# MCU.net
KiCad netlist of a schematic drawn in Altium Designer
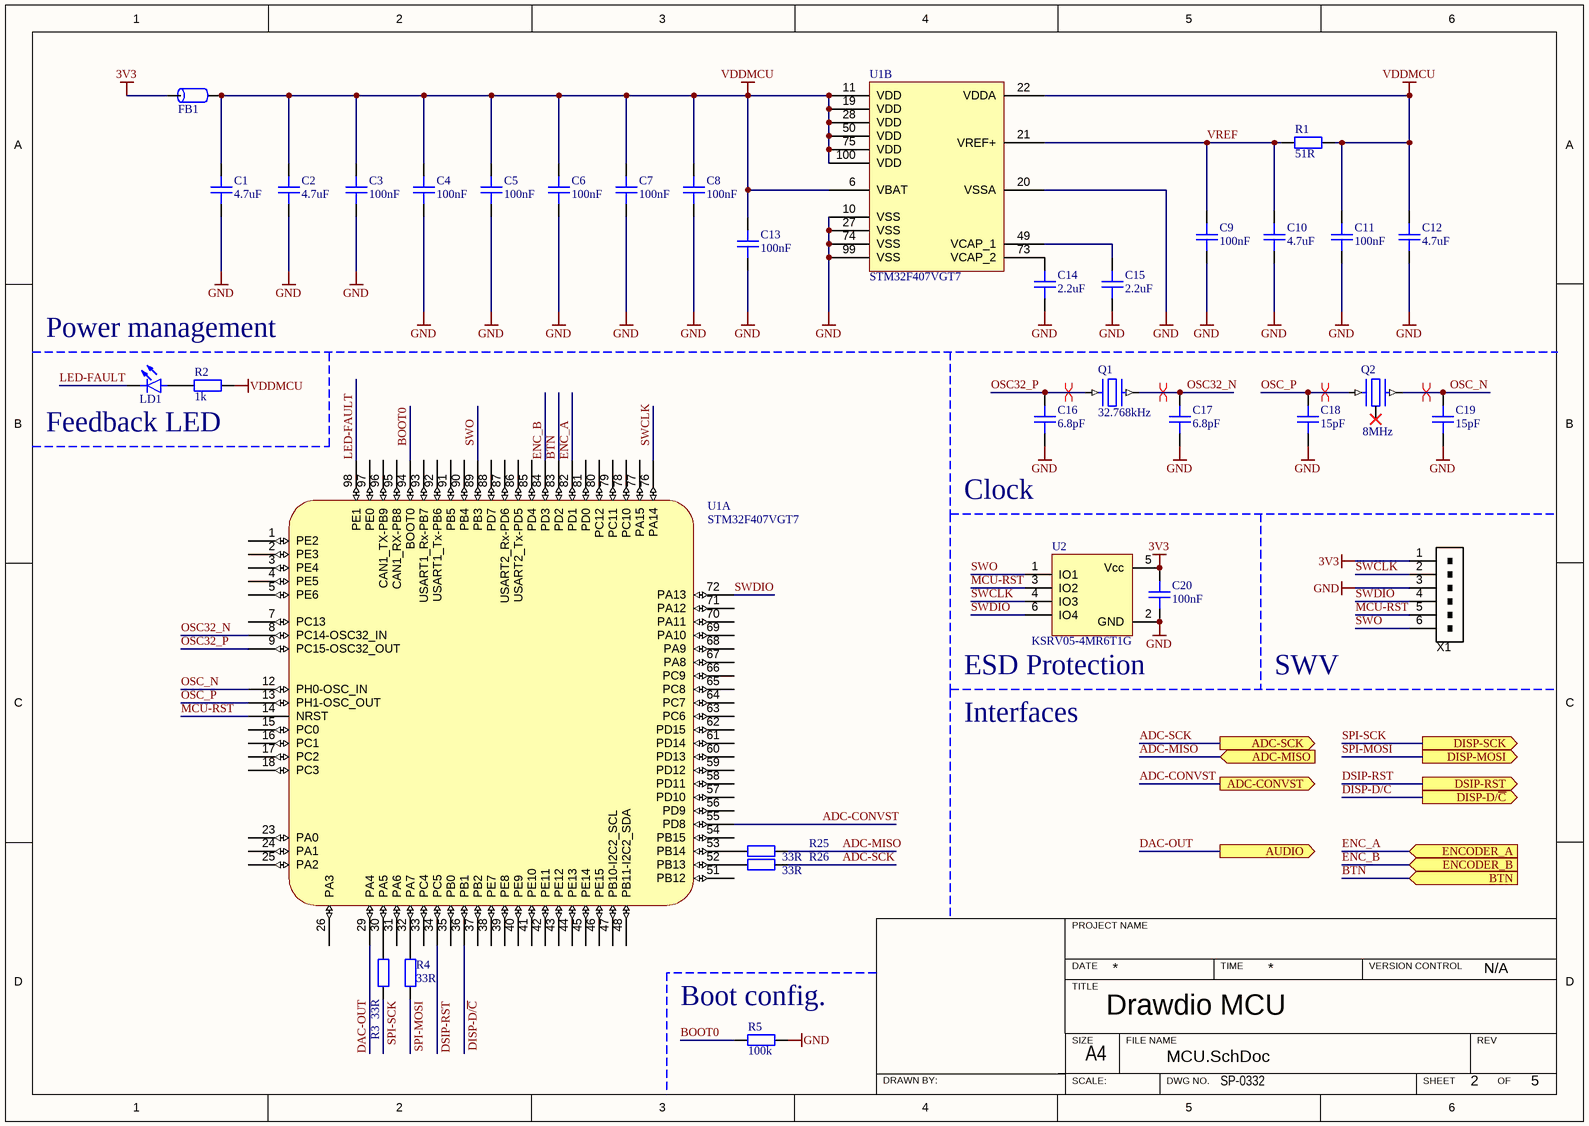
[diagram p0: MCU.SchDoc]

(export (version "E")
  (design (tool "Eeschema 10.0.6"))
  (components
    (comp (ref "C1")
      (value "4.7uF")
      (footprint "CAP-0805")
      (description "Capacitor Non-Polar")
      (libsource (lib "MasterLib") (part "CAP - 0805"))
    )
    (comp (ref "C2")
      (value "4.7uF")
      (footprint "CAP-0805")
      (description "Capacitor Non-Polar")
      (libsource (lib "MasterLib") (part "CAP - 0805"))
    )
    (comp (ref "C3")
      (value "100nF")
      (footprint "CAP-0603")
      (description "Capacitor Non-Polar")
      (libsource (lib "MasterLib") (part "CAP - 0603"))
    )
    (comp (ref "C4")
      (value "100nF")
      (footprint "CAP-0603")
      (description "Capacitor Non-Polar")
      (libsource (lib "MasterLib") (part "CAP - 0603"))
    )
    (comp (ref "C5")
      (value "100nF")
      (footprint "CAP-0603")
      (description "Capacitor Non-Polar")
      (libsource (lib "MasterLib") (part "CAP - 0603"))
    )
    (comp (ref "C6")
      (value "100nF")
      (footprint "CAP-0603")
      (description "Capacitor Non-Polar")
      (libsource (lib "MasterLib") (part "CAP - 0603"))
    )
    (comp (ref "C7")
      (value "100nF")
      (footprint "CAP-0603")
      (description "Capacitor Non-Polar")
      (libsource (lib "MasterLib") (part "CAP - 0603"))
    )
    (comp (ref "C8")
      (value "100nF")
      (footprint "CAP-0603")
      (description "Capacitor Non-Polar")
      (libsource (lib "MasterLib") (part "CAP - 0603"))
    )
    (comp (ref "C9")
      (value "100nF")
      (footprint "CAP-0603")
      (description "Capacitor Non-Polar")
      (libsource (lib "MasterLib") (part "CAP - 0603"))
    )
    (comp (ref "C10")
      (value "4.7uF")
      (footprint "CAP-0805")
      (description "Capacitor Non-Polar")
      (libsource (lib "MasterLib") (part "CAP - 0805"))
    )
    (comp (ref "C11")
      (value "100nF")
      (footprint "CAP-0603")
      (description "Capacitor Non-Polar")
      (libsource (lib "MasterLib") (part "CAP - 0603"))
    )
    (comp (ref "C12")
      (value "4.7uF")
      (footprint "CAP-0805")
      (description "Capacitor Non-Polar")
      (libsource (lib "MasterLib") (part "CAP - 0805"))
    )
    (comp (ref "C13")
      (value "100nF")
      (footprint "CAP-0603")
      (description "Capacitor Non-Polar")
      (libsource (lib "MasterLib") (part "CAP - 0603"))
    )
    (comp (ref "C14")
      (value "2.2uF")
      (footprint "CAP-0805")
      (description "Capacitor Non-Polar")
      (libsource (lib "MasterLib") (part "CAP - 0805"))
    )
    (comp (ref "C15")
      (value "2.2uF")
      (footprint "CAP-0805")
      (description "Capacitor Non-Polar")
      (libsource (lib "MasterLib") (part "CAP - 0805"))
    )
    (comp (ref "C16")
      (value "6.8pF")
      (footprint "CAP-0603")
      (description "Capacitor Non-Polar")
      (libsource (lib "MasterLib") (part "CAP - 0603"))
    )
    (comp (ref "C17")
      (value "6.8pF")
      (footprint "CAP-0603")
      (description "Capacitor Non-Polar")
      (libsource (lib "MasterLib") (part "CAP - 0603"))
    )
    (comp (ref "C18")
      (value "15pF")
      (footprint "CAP-0603")
      (description "Capacitor Non-Polar")
      (libsource (lib "MasterLib") (part "CAP - 0603"))
    )
    (comp (ref "C19")
      (value "15pF")
      (footprint "CAP-0603")
      (description "Capacitor Non-Polar")
      (libsource (lib "MasterLib") (part "CAP - 0603"))
    )
    (comp (ref "C20")
      (value "100nF")
      (footprint "CAP-0603")
      (description "Capacitor Non-Polar")
      (libsource (lib "MasterLib") (part "CAP - 0603"))
    )
    (comp (ref "FB1")
      (value "FB - 0603")
      (footprint "FB-0603")
      (description "Ferrit bead 0603")
      (libsource (lib "MasterLib") (part "FB - 0603"))
    )
    (comp (ref "LD1")
      (value "LED - 0603")
      (footprint "LED-0603")
      (description "Single color LED")
      (libsource (lib "MasterLib") (part "LED - 0603"))
    )
    (comp (ref "Q1")
      (value "32.768kHz")
      (footprint "OSC-3.2x1.5")
      (description "32.768kHz quartz")
      (libsource (lib "MasterLib") (part "OSC - RTC"))
    )
    (comp (ref "Q2")
      (value "8MHz")
      (footprint "OSC-3.2x2.5")
      (description "8MHz quartz")
      (libsource (lib "MasterLib") (part "OSC - MHZ SMD"))
    )
    (comp (ref "R1")
      (value "51R")
      (footprint "RES-0603")
      (description "Resistor")
      (libsource (lib "MasterLib") (part "RES - 0603"))
    )
    (comp (ref "R2")
      (value "1k")
      (footprint "RES-0603")
      (description "Resistor")
      (libsource (lib "") (part "RES - 0603_1"))
    )
    (comp (ref "R3")
      (value "33R")
      (footprint "RES-0603")
      (description "Resistor")
      (libsource (lib "") (part "RES - 0603_1"))
    )
    (comp (ref "R4")
      (value "33R")
      (footprint "RES-0603")
      (description "Resistor")
      (libsource (lib "") (part "RES - 0603_1"))
    )
    (comp (ref "R5")
      (value "100k")
      (footprint "RES-0603")
      (description "Resistor")
      (libsource (lib "") (part "RES - 0603_2"))
    )
    (comp (ref "R25")
      (value "33R")
      (footprint "RES-0603")
      (description "Resistor")
      (libsource (lib "MasterLib") (part "RES - 0603"))
    )
    (comp (ref "R26")
      (value "33R")
      (footprint "RES-0603")
      (description "Resistor")
      (libsource (lib "MasterLib") (part "RES - 0603"))
    )
    (comp (ref "U1")
      (value "STM32F407VGT7")
      (footprint "IC-TQFP-100")
      (libsource (lib "MasterLib") (part "IC - STM32F407VGxx"))
    )
    (comp (ref "U2")
      (value "KSRV05-4MR6T1G")
      (footprint "T-SOT-23-6")
      (description "ESD supressor, max. 28V, 150W")
      (libsource (lib "MasterLib") (part "D - KSRV05"))
    )
    (comp (ref "X1")
      (value "CONN - SWV")
      (footprint "CONN-SWV-THT FEMALE")
      (description "SWD view and program connector")
      (libsource (lib "MasterLib") (part "CONN - SWV"))
    )
  )
  (nets
    (net (code "1") (name "/ADC-CONVST") (class "Default")
      (node (ref "U1") (pin "55") (pinfunction "PD8_55") (pintype "bidirectional"))
    )
    (net (code "2") (name "/ADC-MISO") (class "Default")
      (node (ref "R25") (pin "2") (pinfunction "2_2") (pintype "passive"))
    )
    (net (code "3") (name "/ADC-SCK") (class "Default")
      (node (ref "R26") (pin "2") (pinfunction "2_2") (pintype "passive"))
    )
    (net (code "4") (name "/BOOT0") (class "Default")
      (node (ref "R5") (pin "1") (pinfunction "1_1") (pintype "passive"))
      (node (ref "U1") (pin "94") (pinfunction "BOOT0_94") (pintype "bidirectional"))
    )
    (net (code "5") (name "/BTN") (class "Default")
      (node (ref "U1") (pin "83") (pinfunction "PD2_83") (pintype "bidirectional"))
    )
    (net (code "6") (name "/DAC-OUT") (class "Default")
      (node (ref "U1") (pin "29") (pinfunction "PA4_29") (pintype "bidirectional"))
    )
    (net (code "7") (name "/DISP-D{slash}~{C}") (class "Default")
      (node (ref "U1") (pin "36") (pinfunction "PB1_36") (pintype "bidirectional"))
    )
    (net (code "8") (name "/DSIP-RST") (class "Default")
      (node (ref "U1") (pin "34") (pinfunction "PC5_34") (pintype "bidirectional"))
    )
    (net (code "9") (name "/ENC_A") (class "Default")
      (node (ref "U1") (pin "82") (pinfunction "PD1_82") (pintype "bidirectional"))
    )
    (net (code "10") (name "/ENC_B") (class "Default")
      (node (ref "U1") (pin "84") (pinfunction "PD3_84") (pintype "bidirectional"))
    )
    (net (code "11") (name "/LED-FAULT") (class "Default")
      (node (ref "LD1") (pin "2") (pinfunction "K_2") (pintype "passive"))
      (node (ref "U1") (pin "98") (pinfunction "PE1_98") (pintype "bidirectional"))
    )
    (net (code "12") (name "/MCU-RST") (class "Default")
      (node (ref "U1") (pin "14") (pinfunction "NRST_14") (pintype "passive"))
      (node (ref "U2") (pin "3") (pinfunction "IO2_3") (pintype "passive"))
      (node (ref "X1") (pin "5") (pinfunction "5_5") (pintype "passive"))
    )
    (net (code "13") (name "/OSC32_N") (class "Default")
      (node (ref "C17") (pin "2") (pinfunction "2_2") (pintype "passive"))
      (node (ref "Q1") (pin "4") (pinfunction "4_4") (pintype "output"))
      (node (ref "U1") (pin "8") (pinfunction "PC14-OSC32_IN_8") (pintype "bidirectional"))
    )
    (net (code "14") (name "/OSC32_P") (class "Default")
      (node (ref "C16") (pin "2") (pinfunction "2_2") (pintype "passive"))
      (node (ref "Q1") (pin "1") (pinfunction "1_1") (pintype "input"))
      (node (ref "U1") (pin "9") (pinfunction "PC15-OSC32_OUT_9") (pintype "bidirectional"))
    )
    (net (code "15") (name "/OSC_N") (class "Default")
      (node (ref "C19") (pin "2") (pinfunction "2_2") (pintype "passive"))
      (node (ref "Q2") (pin "2") (pinfunction "2_2") (pintype "output"))
      (node (ref "U1") (pin "12") (pinfunction "PH0-OSC_IN_12") (pintype "bidirectional"))
    )
    (net (code "16") (name "/OSC_P") (class "Default")
      (node (ref "C18") (pin "2") (pinfunction "2_2") (pintype "passive"))
      (node (ref "Q2") (pin "1") (pinfunction "1_1") (pintype "input"))
      (node (ref "U1") (pin "13") (pinfunction "PH1-OSC_OUT_13") (pintype "bidirectional"))
    )
    (net (code "17") (name "/SPI-MOSI") (class "Default")
      (node (ref "R4") (pin "2") (pinfunction "2_2") (pintype "passive"))
    )
    (net (code "18") (name "/SPI-SCK") (class "Default")
      (node (ref "R3") (pin "2") (pinfunction "2_2") (pintype "passive"))
    )
    (net (code "19") (name "/SWCLK") (class "Default")
      (node (ref "U1") (pin "76") (pinfunction "PA14_76") (pintype "bidirectional"))
      (node (ref "U2") (pin "4") (pinfunction "IO3_4") (pintype "passive"))
      (node (ref "X1") (pin "2") (pinfunction "2_2") (pintype "passive"))
    )
    (net (code "20") (name "/SWDIO") (class "Default")
      (node (ref "U1") (pin "72") (pinfunction "PA13_72") (pintype "bidirectional"))
      (node (ref "U2") (pin "6") (pinfunction "IO4_6") (pintype "passive"))
      (node (ref "X1") (pin "4") (pinfunction "4_4") (pintype "passive"))
    )
    (net (code "21") (name "/SWO") (class "Default")
      (node (ref "U1") (pin "89") (pinfunction "PB3_89") (pintype "bidirectional"))
      (node (ref "U2") (pin "1") (pinfunction "IO1_1") (pintype "passive"))
      (node (ref "X1") (pin "6") (pinfunction "6_6") (pintype "passive"))
    )
    (net (code "22") (name "/VREF") (class "Default")
      (node (ref "C10") (pin "2") (pinfunction "2_2") (pintype "passive"))
      (node (ref "C9") (pin "2") (pinfunction "2_2") (pintype "passive"))
      (node (ref "R1") (pin "1") (pinfunction "1_1") (pintype "passive"))
      (node (ref "U1") (pin "21") (pinfunction "VREF+_21") (pintype "power_in"))
    )
    (net (code "23") (name "3V3") (class "Default")
      (node (ref "C20") (pin "2") (pinfunction "2_2") (pintype "passive"))
      (node (ref "FB1") (pin "1") (pinfunction "1_1") (pintype "passive"))
      (node (ref "U2") (pin "5") (pinfunction "Vcc_5") (pintype "passive"))
      (node (ref "X1") (pin "1") (pinfunction "1_1") (pintype "passive"))
    )
    (net (code "24") (name "GND") (class "Default")
      (node (ref "C1") (pin "1") (pinfunction "1_1") (pintype "passive"))
      (node (ref "C10") (pin "1") (pinfunction "1_1") (pintype "passive"))
      (node (ref "C11") (pin "1") (pinfunction "1_1") (pintype "passive"))
      (node (ref "C12") (pin "1") (pinfunction "1_1") (pintype "passive"))
      (node (ref "C13") (pin "1") (pinfunction "1_1") (pintype "passive"))
      (node (ref "C14") (pin "1") (pinfunction "1_1") (pintype "passive"))
      (node (ref "C15") (pin "1") (pinfunction "1_1") (pintype "passive"))
      (node (ref "C16") (pin "1") (pinfunction "1_1") (pintype "passive"))
      (node (ref "C17") (pin "1") (pinfunction "1_1") (pintype "passive"))
      (node (ref "C18") (pin "1") (pinfunction "1_1") (pintype "passive"))
      (node (ref "C19") (pin "1") (pinfunction "1_1") (pintype "passive"))
      (node (ref "C2") (pin "1") (pinfunction "1_1") (pintype "passive"))
      (node (ref "C20") (pin "1") (pinfunction "1_1") (pintype "passive"))
      (node (ref "C3") (pin "1") (pinfunction "1_1") (pintype "passive"))
      (node (ref "C4") (pin "1") (pinfunction "1_1") (pintype "passive"))
      (node (ref "C5") (pin "1") (pinfunction "1_1") (pintype "passive"))
      (node (ref "C6") (pin "1") (pinfunction "1_1") (pintype "passive"))
      (node (ref "C7") (pin "1") (pinfunction "1_1") (pintype "passive"))
      (node (ref "C8") (pin "1") (pinfunction "1_1") (pintype "passive"))
      (node (ref "C9") (pin "1") (pinfunction "1_1") (pintype "passive"))
      (node (ref "R5") (pin "2") (pinfunction "2_2") (pintype "passive"))
      (node (ref "U1") (pin "10") (pinfunction "VSS_10") (pintype "power_in"))
      (node (ref "U1") (pin "20") (pinfunction "VSSA_20") (pintype "power_in"))
      (node (ref "U1") (pin "27") (pinfunction "VSS_27") (pintype "power_in"))
      (node (ref "U1") (pin "74") (pinfunction "VSS_74") (pintype "power_in"))
      (node (ref "U1") (pin "99") (pinfunction "VSS_99") (pintype "power_in"))
      (node (ref "U2") (pin "2") (pinfunction "GND_2") (pintype "passive"))
      (node (ref "X1") (pin "3") (pinfunction "3_3") (pintype "passive"))
    )
    (net (code "25") (name "Net-(LD1-A)") (class "Default")
      (node (ref "LD1") (pin "1") (pinfunction "A_1") (pintype "passive"))
      (node (ref "R2") (pin "2") (pinfunction "2_2") (pintype "passive"))
    )
    (net (code "26") (name "Net-(U1A-PA5)") (class "Default")
      (node (ref "R3") (pin "1") (pinfunction "1_1") (pintype "passive"))
      (node (ref "U1") (pin "30") (pinfunction "PA5_30") (pintype "bidirectional"))
    )
    (net (code "27") (name "Net-(U1A-PA7)") (class "Default")
      (node (ref "R4") (pin "1") (pinfunction "1_1") (pintype "passive"))
      (node (ref "U1") (pin "32") (pinfunction "PA7_32") (pintype "bidirectional"))
    )
    (net (code "28") (name "Net-(U1A-PB13)") (class "Default")
      (node (ref "R26") (pin "1") (pinfunction "1_1") (pintype "passive"))
      (node (ref "U1") (pin "52") (pinfunction "PB13_52") (pintype "bidirectional"))
    )
    (net (code "29") (name "Net-(U1A-PB14)") (class "Default")
      (node (ref "R25") (pin "1") (pinfunction "1_1") (pintype "passive"))
      (node (ref "U1") (pin "53") (pinfunction "PB14_53") (pintype "bidirectional"))
    )
    (net (code "30") (name "Net-(U1B-VCAP_1)") (class "Default")
      (node (ref "C15") (pin "2") (pinfunction "2_2") (pintype "passive"))
      (node (ref "U1") (pin "49") (pinfunction "VCAP_1_49") (pintype "power_in"))
    )
    (net (code "31") (name "Net-(U1B-VCAP_2)") (class "Default")
      (node (ref "C14") (pin "2") (pinfunction "2_2") (pintype "passive"))
      (node (ref "U1") (pin "73") (pinfunction "VCAP_2_73") (pintype "power_in"))
    )
    (net (code "32") (name "VDDMCU") (class "Default")
      (node (ref "C1") (pin "2") (pinfunction "2_2") (pintype "passive"))
      (node (ref "C11") (pin "2") (pinfunction "2_2") (pintype "passive"))
      (node (ref "C12") (pin "2") (pinfunction "2_2") (pintype "passive"))
      (node (ref "C13") (pin "2") (pinfunction "2_2") (pintype "passive"))
      (node (ref "C2") (pin "2") (pinfunction "2_2") (pintype "passive"))
      (node (ref "C3") (pin "2") (pinfunction "2_2") (pintype "passive"))
      (node (ref "C4") (pin "2") (pinfunction "2_2") (pintype "passive"))
      (node (ref "C5") (pin "2") (pinfunction "2_2") (pintype "passive"))
      (node (ref "C6") (pin "2") (pinfunction "2_2") (pintype "passive"))
      (node (ref "C7") (pin "2") (pinfunction "2_2") (pintype "passive"))
      (node (ref "C8") (pin "2") (pinfunction "2_2") (pintype "passive"))
      (node (ref "FB1") (pin "2") (pinfunction "2_2") (pintype "passive"))
      (node (ref "R1") (pin "2") (pinfunction "2_2") (pintype "passive"))
      (node (ref "R2") (pin "1") (pinfunction "1_1") (pintype "passive"))
      (node (ref "U1") (pin "100") (pinfunction "VDD_100") (pintype "power_in"))
      (node (ref "U1") (pin "11") (pinfunction "VDD_11") (pintype "power_in"))
      (node (ref "U1") (pin "19") (pinfunction "VDD_19") (pintype "power_in"))
      (node (ref "U1") (pin "22") (pinfunction "VDDA_22") (pintype "power_in"))
      (node (ref "U1") (pin "28") (pinfunction "VDD_28") (pintype "power_in"))
      (node (ref "U1") (pin "50") (pinfunction "VDD_50") (pintype "power_in"))
      (node (ref "U1") (pin "6") (pinfunction "VBAT_6") (pintype "power_in"))
      (node (ref "U1") (pin "75") (pinfunction "VDD_75") (pintype "power_in"))
    )
    (net (code "33") (name "unconnected-(Q2-Pad3)") (class "Default")
      (node (ref "Q2") (pin "3") (pinfunction "3_3") (pintype "passive+no_connect"))
    )
    (net (code "34") (name "unconnected-(U1A-CAN1_RX-PB8-Pad95)") (class "Default")
      (node (ref "U1") (pin "95") (pinfunction "CAN1_RX-PB8_95") (pintype "bidirectional"))
    )
    (net (code "35") (name "unconnected-(U1A-CAN1_TX-PB9-Pad96)") (class "Default")
      (node (ref "U1") (pin "96") (pinfunction "CAN1_TX-PB9_96") (pintype "bidirectional"))
    )
    (net (code "36") (name "unconnected-(U1A-PA0-Pad23)") (class "Default")
      (node (ref "U1") (pin "23") (pinfunction "PA0_23") (pintype "bidirectional"))
    )
    (net (code "37") (name "unconnected-(U1A-PA1-Pad24)") (class "Default")
      (node (ref "U1") (pin "24") (pinfunction "PA1_24") (pintype "bidirectional"))
    )
    (net (code "38") (name "unconnected-(U1A-PA2-Pad25)") (class "Default")
      (node (ref "U1") (pin "25") (pinfunction "PA2_25") (pintype "bidirectional"))
    )
    (net (code "39") (name "unconnected-(U1A-PA3-Pad26)") (class "Default")
      (node (ref "U1") (pin "26") (pinfunction "PA3_26") (pintype "bidirectional"))
    )
    (net (code "40") (name "unconnected-(U1A-PA6-Pad31)") (class "Default")
      (node (ref "U1") (pin "31") (pinfunction "PA6_31") (pintype "bidirectional"))
    )
    (net (code "41") (name "unconnected-(U1A-PA8-Pad67)") (class "Default")
      (node (ref "U1") (pin "67") (pinfunction "PA8_67") (pintype "bidirectional"))
    )
    (net (code "42") (name "unconnected-(U1A-PA9-Pad68)") (class "Default")
      (node (ref "U1") (pin "68") (pinfunction "PA9_68") (pintype "bidirectional"))
    )
    (net (code "43") (name "unconnected-(U1A-PA10-Pad69)") (class "Default")
      (node (ref "U1") (pin "69") (pinfunction "PA10_69") (pintype "bidirectional"))
    )
    (net (code "44") (name "unconnected-(U1A-PA11-Pad70)") (class "Default")
      (node (ref "U1") (pin "70") (pinfunction "PA11_70") (pintype "bidirectional"))
    )
    (net (code "45") (name "unconnected-(U1A-PA12-Pad71)") (class "Default")
      (node (ref "U1") (pin "71") (pinfunction "PA12_71") (pintype "bidirectional"))
    )
    (net (code "46") (name "unconnected-(U1A-PA15-Pad77)") (class "Default")
      (node (ref "U1") (pin "77") (pinfunction "PA15_77") (pintype "bidirectional"))
    )
    (net (code "47") (name "unconnected-(U1A-PB0-Pad35)") (class "Default")
      (node (ref "U1") (pin "35") (pinfunction "PB0_35") (pintype "bidirectional"))
    )
    (net (code "48") (name "unconnected-(U1A-PB2-Pad37)") (class "Default")
      (node (ref "U1") (pin "37") (pinfunction "PB2_37") (pintype "bidirectional"))
    )
    (net (code "49") (name "unconnected-(U1A-PB4-Pad90)") (class "Default")
      (node (ref "U1") (pin "90") (pinfunction "PB4_90") (pintype "bidirectional"))
    )
    (net (code "50") (name "unconnected-(U1A-PB5-Pad91)") (class "Default")
      (node (ref "U1") (pin "91") (pinfunction "PB5_91") (pintype "bidirectional"))
    )
    (net (code "51") (name "unconnected-(U1A-PB10-I2C2_SCL-Pad47)") (class "Default")
      (node (ref "U1") (pin "47") (pinfunction "PB10-I2C2_SCL_47") (pintype "bidirectional"))
    )
    (net (code "52") (name "unconnected-(U1A-PB11-I2C2_SDA-Pad48)") (class "Default")
      (node (ref "U1") (pin "48") (pinfunction "PB11-I2C2_SDA_48") (pintype "bidirectional"))
    )
    (net (code "53") (name "unconnected-(U1A-PB12-Pad51)") (class "Default")
      (node (ref "U1") (pin "51") (pinfunction "PB12_51") (pintype "bidirectional"))
    )
    (net (code "54") (name "unconnected-(U1A-PB15-Pad54)") (class "Default")
      (node (ref "U1") (pin "54") (pinfunction "PB15_54") (pintype "bidirectional"))
    )
    (net (code "55") (name "unconnected-(U1A-PC0-Pad15)") (class "Default")
      (node (ref "U1") (pin "15") (pinfunction "PC0_15") (pintype "bidirectional"))
    )
    (net (code "56") (name "unconnected-(U1A-PC1-Pad16)") (class "Default")
      (node (ref "U1") (pin "16") (pinfunction "PC1_16") (pintype "bidirectional"))
    )
    (net (code "57") (name "unconnected-(U1A-PC2-Pad17)") (class "Default")
      (node (ref "U1") (pin "17") (pinfunction "PC2_17") (pintype "bidirectional"))
    )
    (net (code "58") (name "unconnected-(U1A-PC3-Pad18)") (class "Default")
      (node (ref "U1") (pin "18") (pinfunction "PC3_18") (pintype "bidirectional"))
    )
    (net (code "59") (name "unconnected-(U1A-PC4-Pad33)") (class "Default")
      (node (ref "U1") (pin "33") (pinfunction "PC4_33") (pintype "bidirectional"))
    )
    (net (code "60") (name "unconnected-(U1A-PC6-Pad63)") (class "Default")
      (node (ref "U1") (pin "63") (pinfunction "PC6_63") (pintype "bidirectional"))
    )
    (net (code "61") (name "unconnected-(U1A-PC7-Pad64)") (class "Default")
      (node (ref "U1") (pin "64") (pinfunction "PC7_64") (pintype "bidirectional"))
    )
    (net (code "62") (name "unconnected-(U1A-PC8-Pad65)") (class "Default")
      (node (ref "U1") (pin "65") (pinfunction "PC8_65") (pintype "bidirectional"))
    )
    (net (code "63") (name "unconnected-(U1A-PC9-Pad66)") (class "Default")
      (node (ref "U1") (pin "66") (pinfunction "PC9_66") (pintype "bidirectional"))
    )
    (net (code "64") (name "unconnected-(U1A-PC10-Pad78)") (class "Default")
      (node (ref "U1") (pin "78") (pinfunction "PC10_78") (pintype "bidirectional"))
    )
    (net (code "65") (name "unconnected-(U1A-PC11-Pad79)") (class "Default")
      (node (ref "U1") (pin "79") (pinfunction "PC11_79") (pintype "bidirectional"))
    )
    (net (code "66") (name "unconnected-(U1A-PC12-Pad80)") (class "Default")
      (node (ref "U1") (pin "80") (pinfunction "PC12_80") (pintype "bidirectional"))
    )
    (net (code "67") (name "unconnected-(U1A-PC13-Pad7)") (class "Default")
      (node (ref "U1") (pin "7") (pinfunction "PC13_7") (pintype "bidirectional"))
    )
    (net (code "68") (name "unconnected-(U1A-PD0-Pad81)") (class "Default")
      (node (ref "U1") (pin "81") (pinfunction "PD0_81") (pintype "bidirectional"))
    )
    (net (code "69") (name "unconnected-(U1A-PD4-Pad85)") (class "Default")
      (node (ref "U1") (pin "85") (pinfunction "PD4_85") (pintype "bidirectional"))
    )
    (net (code "70") (name "unconnected-(U1A-PD7-Pad88)") (class "Default")
      (node (ref "U1") (pin "88") (pinfunction "PD7_88") (pintype "bidirectional"))
    )
    (net (code "71") (name "unconnected-(U1A-PD9-Pad56)") (class "Default")
      (node (ref "U1") (pin "56") (pinfunction "PD9_56") (pintype "bidirectional"))
    )
    (net (code "72") (name "unconnected-(U1A-PD10-Pad57)") (class "Default")
      (node (ref "U1") (pin "57") (pinfunction "PD10_57") (pintype "bidirectional"))
    )
    (net (code "73") (name "unconnected-(U1A-PD11-Pad58)") (class "Default")
      (node (ref "U1") (pin "58") (pinfunction "PD11_58") (pintype "bidirectional"))
    )
    (net (code "74") (name "unconnected-(U1A-PD12-Pad59)") (class "Default")
      (node (ref "U1") (pin "59") (pinfunction "PD12_59") (pintype "bidirectional"))
    )
    (net (code "75") (name "unconnected-(U1A-PD13-Pad60)") (class "Default")
      (node (ref "U1") (pin "60") (pinfunction "PD13_60") (pintype "bidirectional"))
    )
    (net (code "76") (name "unconnected-(U1A-PD14-Pad61)") (class "Default")
      (node (ref "U1") (pin "61") (pinfunction "PD14_61") (pintype "bidirectional"))
    )
    (net (code "77") (name "unconnected-(U1A-PD15-Pad62)") (class "Default")
      (node (ref "U1") (pin "62") (pinfunction "PD15_62") (pintype "bidirectional"))
    )
    (net (code "78") (name "unconnected-(U1A-PE0-Pad97)") (class "Default")
      (node (ref "U1") (pin "97") (pinfunction "PE0_97") (pintype "bidirectional"))
    )
    (net (code "79") (name "unconnected-(U1A-PE2-Pad1)") (class "Default")
      (node (ref "U1") (pin "1") (pinfunction "PE2_1") (pintype "bidirectional"))
    )
    (net (code "80") (name "unconnected-(U1A-PE3-Pad2)") (class "Default")
      (node (ref "U1") (pin "2") (pinfunction "PE3_2") (pintype "bidirectional"))
    )
    (net (code "81") (name "unconnected-(U1A-PE4-Pad3)") (class "Default")
      (node (ref "U1") (pin "3") (pinfunction "PE4_3") (pintype "bidirectional"))
    )
    (net (code "82") (name "unconnected-(U1A-PE5-Pad4)") (class "Default")
      (node (ref "U1") (pin "4") (pinfunction "PE5_4") (pintype "bidirectional"))
    )
    (net (code "83") (name "unconnected-(U1A-PE6-Pad5)") (class "Default")
      (node (ref "U1") (pin "5") (pinfunction "PE6_5") (pintype "bidirectional"))
    )
    (net (code "84") (name "unconnected-(U1A-PE7-Pad38)") (class "Default")
      (node (ref "U1") (pin "38") (pinfunction "PE7_38") (pintype "bidirectional"))
    )
    (net (code "85") (name "unconnected-(U1A-PE8-Pad39)") (class "Default")
      (node (ref "U1") (pin "39") (pinfunction "PE8_39") (pintype "bidirectional"))
    )
    (net (code "86") (name "unconnected-(U1A-PE9-Pad40)") (class "Default")
      (node (ref "U1") (pin "40") (pinfunction "PE9_40") (pintype "bidirectional"))
    )
    (net (code "87") (name "unconnected-(U1A-PE10-Pad41)") (class "Default")
      (node (ref "U1") (pin "41") (pinfunction "PE10_41") (pintype "bidirectional"))
    )
    (net (code "88") (name "unconnected-(U1A-PE11-Pad42)") (class "Default")
      (node (ref "U1") (pin "42") (pinfunction "PE11_42") (pintype "bidirectional"))
    )
    (net (code "89") (name "unconnected-(U1A-PE12-Pad43)") (class "Default")
      (node (ref "U1") (pin "43") (pinfunction "PE12_43") (pintype "bidirectional"))
    )
    (net (code "90") (name "unconnected-(U1A-PE13-Pad44)") (class "Default")
      (node (ref "U1") (pin "44") (pinfunction "PE13_44") (pintype "bidirectional"))
    )
    (net (code "91") (name "unconnected-(U1A-PE14-Pad45)") (class "Default")
      (node (ref "U1") (pin "45") (pinfunction "PE14_45") (pintype "bidirectional"))
    )
    (net (code "92") (name "unconnected-(U1A-PE15-Pad46)") (class "Default")
      (node (ref "U1") (pin "46") (pinfunction "PE15_46") (pintype "bidirectional"))
    )
    (net (code "93") (name "unconnected-(U1A-USART1_Rx-PB7-Pad93)") (class "Default")
      (node (ref "U1") (pin "93") (pinfunction "USART1_Rx-PB7_93") (pintype "bidirectional"))
    )
    (net (code "94") (name "unconnected-(U1A-USART1_Tx-PB6-Pad92)") (class "Default")
      (node (ref "U1") (pin "92") (pinfunction "USART1_Tx-PB6_92") (pintype "bidirectional"))
    )
    (net (code "95") (name "unconnected-(U1A-USART2_Rx-PD6-Pad87)") (class "Default")
      (node (ref "U1") (pin "87") (pinfunction "USART2_Rx-PD6_87") (pintype "bidirectional"))
    )
    (net (code "96") (name "unconnected-(U1A-USART2_Tx-PD5-Pad86)") (class "Default")
      (node (ref "U1") (pin "86") (pinfunction "USART2_Tx-PD5_86") (pintype "bidirectional"))
    )
  )
)
